# SparkFun_RFM97CW_Breakout.net
KiCad netlist of a schematic drawn in EAGLE
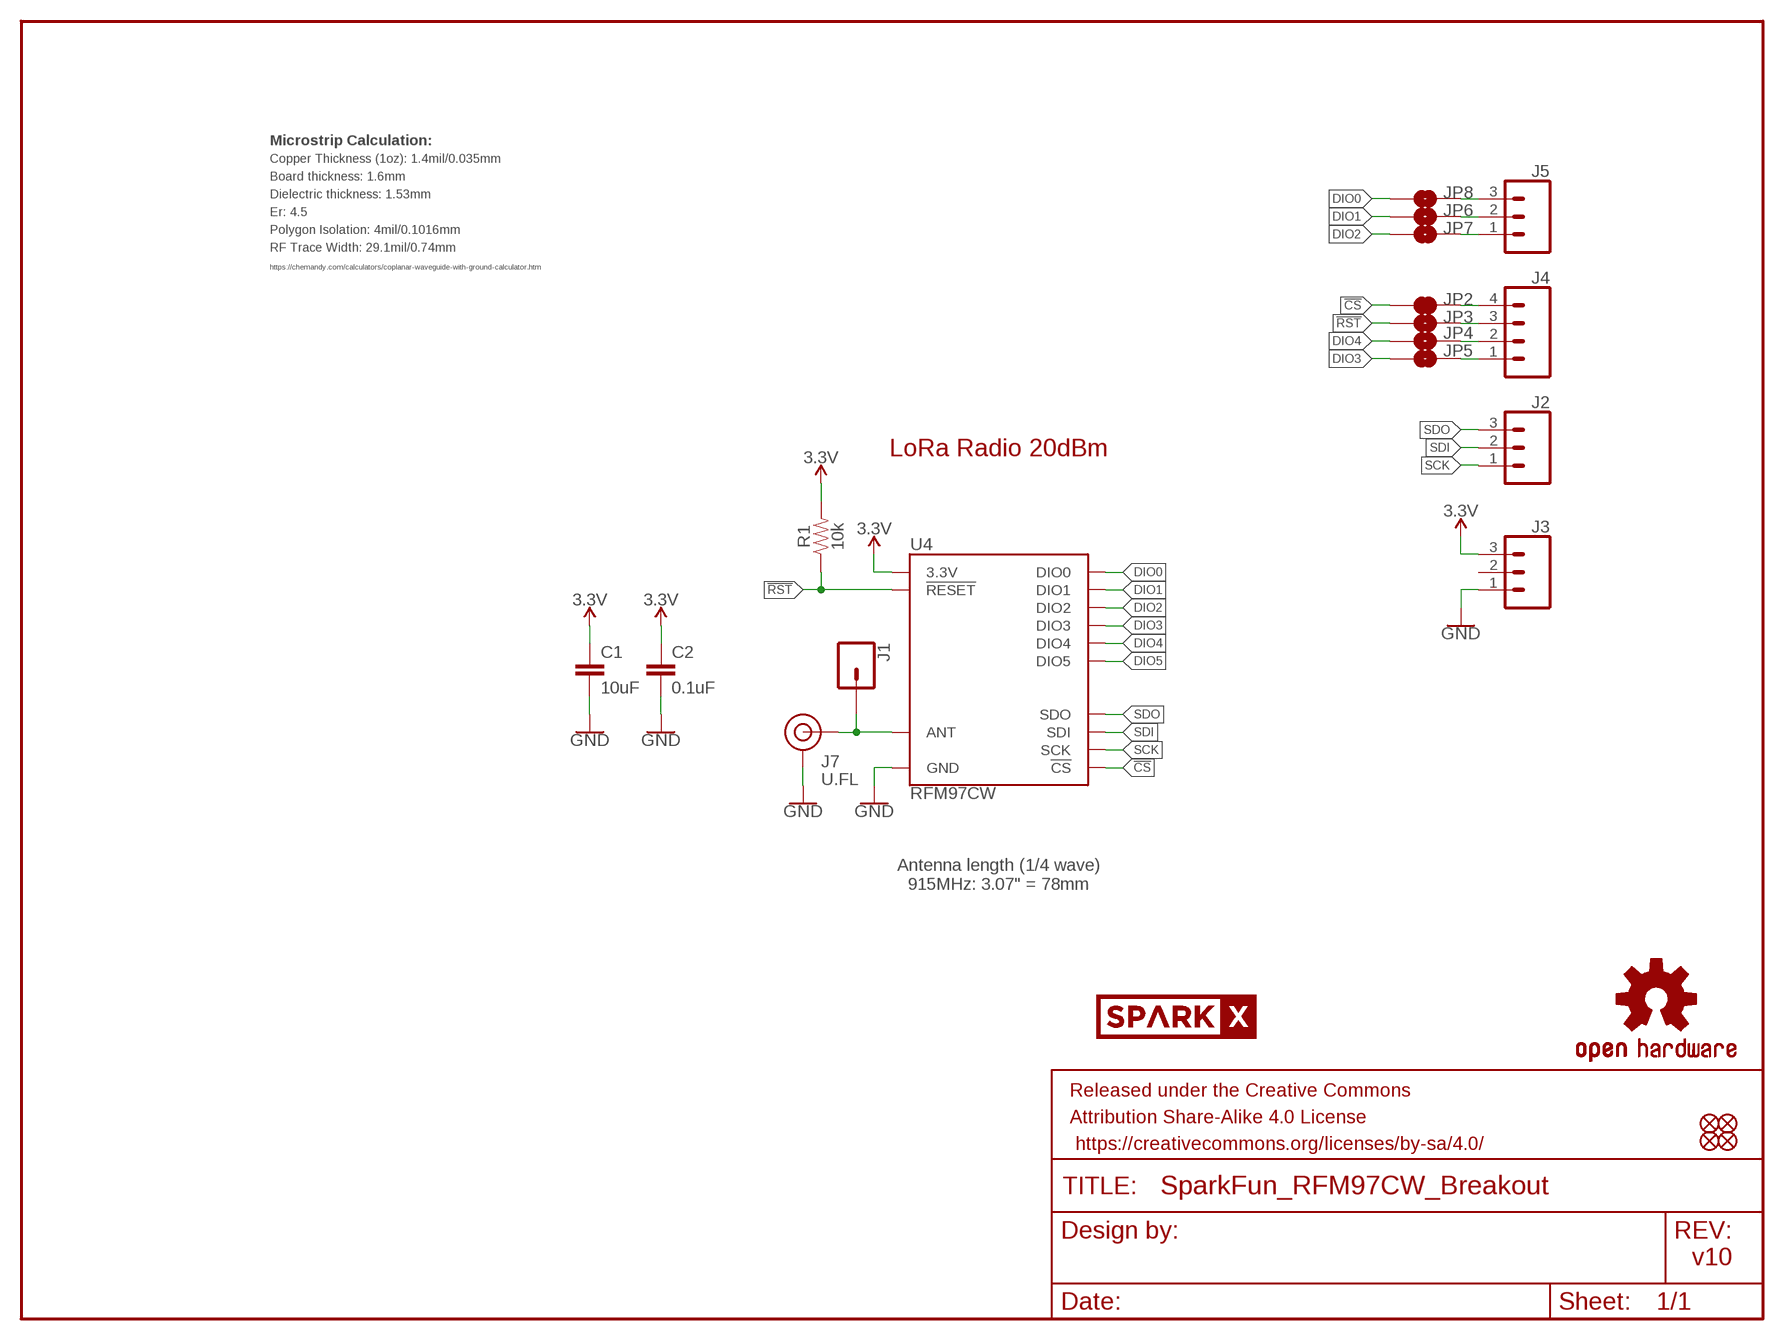
[diagram p0: schematic, sheet 1]

(export (version "E")
  (design (tool "Eeschema 10.0.6"))
  (components
    (comp (ref "C1")
      (value "10uF")
      (footprint "eagle-import:0603")
      (libsource (lib "eagle-import") (part "10UF-0603-6.3V-20%"))
    )
    (comp (ref "C2")
      (value "0.1uF")
      (footprint "eagle-import:0603")
      (libsource (lib "eagle-import") (part "0.1UF-0603-25V-(+80/-20%)"))
    )
    (comp (ref "FID1")
      (value "FIDUCIAL1X2")
      (footprint "eagle-import:FIDUCIAL-1X2")
      (libsource (lib "eagle-import") (part "FIDUCIAL1X2"))
    )
    (comp (ref "FID2")
      (value "FIDUCIAL1X2")
      (footprint "eagle-import:FIDUCIAL-1X2")
      (libsource (lib "eagle-import") (part "FIDUCIAL1X2"))
    )
    (comp (ref "FID3")
      (value "FIDUCIAL1X2")
      (footprint "eagle-import:FIDUCIAL-1X2")
      (libsource (lib "eagle-import") (part "FIDUCIAL1X2"))
    )
    (comp (ref "FID4")
      (value "FIDUCIAL1X2")
      (footprint "eagle-import:FIDUCIAL-1X2")
      (libsource (lib "eagle-import") (part "FIDUCIAL1X2"))
    )
    (comp (ref "FRAME1")
      (value "FRAME-LETTER")
      (footprint "eagle-import:CREATIVE_COMMONS")
      (libsource (lib "eagle-import") (part "FRAME-LETTER"))
    )
    (comp (ref "J1")
      (value "CONN_01PTH_NO_SILK_YES_STOP")
      (footprint "eagle-import:1X01_NO_SILK")
      (libsource (lib "eagle-import") (part "CONN_01PTH_NO_SILK_YES_STOP"))
    )
    (comp (ref "J2")
      (value "CONN_031X03_NO_SILK")
      (footprint "eagle-import:1X03_NO_SILK")
      (libsource (lib "eagle-import") (part "CONN_031X03_NO_SILK"))
    )
    (comp (ref "J3")
      (value "CONN_031X03_NO_SILK")
      (footprint "eagle-import:1X03_NO_SILK")
      (libsource (lib "eagle-import") (part "CONN_031X03_NO_SILK"))
    )
    (comp (ref "J4")
      (value "CONN_041X04_NO_SILK")
      (footprint "eagle-import:1X04_NO_SILK")
      (libsource (lib "eagle-import") (part "CONN_041X04_NO_SILK"))
    )
    (comp (ref "J5")
      (value "CONN_031X03_NO_SILK")
      (footprint "eagle-import:1X03_NO_SILK")
      (libsource (lib "eagle-import") (part "CONN_031X03_NO_SILK"))
    )
    (comp (ref "J7")
      (value "U.FL")
      (footprint "eagle-import:U.FL")
      (libsource (lib "eagle-import") (part "U.FL2PIN"))
    )
    (comp (ref "JP2")
      (value "JUMPER-SMT_2_NC_TRACE_NO-SILK")
      (footprint "eagle-import:SMT-JUMPER_2_NC_TRACE_NO-SILK")
      (libsource (lib "eagle-import") (part "JUMPER-SMT_2_NC_TRACE_NO-SILK"))
    )
    (comp (ref "JP3")
      (value "JUMPER-SMT_2_NO_NO-SILK")
      (footprint "eagle-import:SMT-JUMPER_2_NO_NO-SILK")
      (libsource (lib "eagle-import") (part "JUMPER-SMT_2_NO_NO-SILK"))
    )
    (comp (ref "JP4")
      (value "JUMPER-SMT_2_NO_NO-SILK")
      (footprint "eagle-import:SMT-JUMPER_2_NO_NO-SILK")
      (libsource (lib "eagle-import") (part "JUMPER-SMT_2_NO_NO-SILK"))
    )
    (comp (ref "JP5")
      (value "JUMPER-SMT_2_NO_NO-SILK")
      (footprint "eagle-import:SMT-JUMPER_2_NO_NO-SILK")
      (libsource (lib "eagle-import") (part "JUMPER-SMT_2_NO_NO-SILK"))
    )
    (comp (ref "JP6")
      (value "JUMPER-SMT_2_NO_NO-SILK")
      (footprint "eagle-import:SMT-JUMPER_2_NO_NO-SILK")
      (libsource (lib "eagle-import") (part "JUMPER-SMT_2_NO_NO-SILK"))
    )
    (comp (ref "JP7")
      (value "JUMPER-SMT_2_NO_NO-SILK")
      (footprint "eagle-import:SMT-JUMPER_2_NO_NO-SILK")
      (libsource (lib "eagle-import") (part "JUMPER-SMT_2_NO_NO-SILK"))
    )
    (comp (ref "JP8")
      (value "JUMPER-SMT_2_NO_NO-SILK")
      (footprint "eagle-import:SMT-JUMPER_2_NO_NO-SILK")
      (libsource (lib "eagle-import") (part "JUMPER-SMT_2_NO_NO-SILK"))
    )
    (comp (ref "LOGO2")
      (value "OSHW-LOGOS")
      (footprint "eagle-import:OSHW-LOGO-S")
      (libsource (lib "eagle-import") (part "OSHW-LOGOS"))
    )
    (comp (ref "R1")
      (value "10k")
      (footprint "eagle-import:0603")
      (libsource (lib "eagle-import") (part "10KOHM-0603-1/10W-1%"))
    )
    (comp (ref "U$22")
      (value "SPARKX-LOGO5")
      (footprint "eagle-import:SPARKX-LARGE")
      (libsource (lib "eagle-import") (part "SPARKX-LOGO5"))
    )
    (comp (ref "U4")
      (value "RFM97CW")
      (footprint "eagle-import:RFM97")
      (libsource (lib "eagle-import") (part "RFM9XRFM97"))
    )
  )
  (nets
    (net (code "1") (name "/~{CS}") (class "Default")
      (node (ref "JP2") (pin "1") (pinfunction "1_1") (pintype "passive"))
      (node (ref "U4") (pin "!CS!") (pinfunction "~{CS}_!CS!") (pintype "bidirectional"))
    )
    (net (code "2") (name "/~{RST}") (class "Default")
      (node (ref "JP3") (pin "1") (pinfunction "1_1") (pintype "passive"))
      (node (ref "R1") (pin "1") (pinfunction "1_1") (pintype "passive"))
      (node (ref "U4") (pin "!RST") (pinfunction "~{RESET}_!RST") (pintype "bidirectional"))
    )
    (net (code "3") (name "3.3V") (class "Default")
      (node (ref "C1") (pin "1") (pinfunction "1_1") (pintype "passive"))
      (node (ref "C2") (pin "1") (pinfunction "1_1") (pintype "passive"))
      (node (ref "J3") (pin "3") (pinfunction "3_3") (pintype "passive"))
      (node (ref "R1") (pin "2") (pinfunction "2_2") (pintype "passive"))
      (node (ref "U4") (pin "3V3") (pinfunction "3.3V_3V3") (pintype "bidirectional"))
    )
    (net (code "4") (name "DIO0") (class "Default")
      (node (ref "JP8") (pin "1") (pinfunction "1_1") (pintype "passive"))
      (node (ref "U4") (pin "DIO0") (pinfunction "DIO0_DIO0") (pintype "bidirectional"))
    )
    (net (code "5") (name "DIO1") (class "Default")
      (node (ref "JP6") (pin "1") (pinfunction "1_1") (pintype "passive"))
      (node (ref "U4") (pin "DIO1") (pinfunction "DIO1_DIO1") (pintype "bidirectional"))
    )
    (net (code "6") (name "DIO2") (class "Default")
      (node (ref "JP7") (pin "1") (pinfunction "1_1") (pintype "passive"))
      (node (ref "U4") (pin "DIO2") (pinfunction "DIO2_DIO2") (pintype "bidirectional"))
    )
    (net (code "7") (name "DIO3") (class "Default")
      (node (ref "JP5") (pin "1") (pinfunction "1_1") (pintype "passive"))
      (node (ref "U4") (pin "DIO3") (pinfunction "DIO3_DIO3") (pintype "bidirectional"))
    )
    (net (code "8") (name "DIO4") (class "Default")
      (node (ref "JP4") (pin "1") (pinfunction "1_1") (pintype "passive"))
      (node (ref "U4") (pin "DIO4") (pinfunction "DIO4_DIO4") (pintype "bidirectional"))
    )
    (net (code "9") (name "DIO5") (class "Default")
      (node (ref "U4") (pin "DIO5") (pinfunction "DIO5_DIO5") (pintype "bidirectional"))
    )
    (net (code "10") (name "GND") (class "Default")
      (node (ref "C1") (pin "2") (pinfunction "2_2") (pintype "passive"))
      (node (ref "C2") (pin "2") (pinfunction "2_2") (pintype "passive"))
      (node (ref "J3") (pin "1") (pinfunction "1_1") (pintype "passive"))
      (node (ref "J7") (pin "1") (pinfunction "GND_1") (pintype "bidirectional"))
      (node (ref "J7") (pin "2") (pinfunction "GND_2") (pintype "bidirectional"))
      (node (ref "U4") (pin "GND") (pinfunction "GND_GND") (pintype "bidirectional"))
      (node (ref "U4") (pin "GND@1") (pinfunction "GND_GND@1") (pintype "bidirectional"))
      (node (ref "U4") (pin "GND@2") (pinfunction "GND_GND@2") (pintype "bidirectional"))
    )
    (net (code "11") (name "Net-(J4-Pad1)") (class "Default")
      (node (ref "J4") (pin "1") (pinfunction "1_1") (pintype "passive"))
      (node (ref "JP5") (pin "2") (pinfunction "2_2") (pintype "passive"))
    )
    (net (code "12") (name "Net-(J4-Pad2)") (class "Default")
      (node (ref "J4") (pin "2") (pinfunction "2_2") (pintype "passive"))
      (node (ref "JP4") (pin "2") (pinfunction "2_2") (pintype "passive"))
    )
    (net (code "13") (name "Net-(J4-Pad3)") (class "Default")
      (node (ref "J4") (pin "3") (pinfunction "3_3") (pintype "passive"))
      (node (ref "JP3") (pin "2") (pinfunction "2_2") (pintype "passive"))
    )
    (net (code "14") (name "Net-(J4-Pad4)") (class "Default")
      (node (ref "J4") (pin "4") (pinfunction "4_4") (pintype "passive"))
      (node (ref "JP2") (pin "2") (pinfunction "2_2") (pintype "passive"))
    )
    (net (code "15") (name "Net-(J5-Pad1)") (class "Default")
      (node (ref "J5") (pin "1") (pinfunction "1_1") (pintype "passive"))
      (node (ref "JP7") (pin "2") (pinfunction "2_2") (pintype "passive"))
    )
    (net (code "16") (name "Net-(J5-Pad2)") (class "Default")
      (node (ref "J5") (pin "2") (pinfunction "2_2") (pintype "passive"))
      (node (ref "JP6") (pin "2") (pinfunction "2_2") (pintype "passive"))
    )
    (net (code "17") (name "Net-(J5-Pad3)") (class "Default")
      (node (ref "J5") (pin "3") (pinfunction "3_3") (pintype "passive"))
      (node (ref "JP8") (pin "2") (pinfunction "2_2") (pintype "passive"))
    )
    (net (code "18") (name "Net-(J7-SIGNAL)") (class "Default")
      (node (ref "J1") (pin "1") (pinfunction "1_1") (pintype "passive"))
      (node (ref "J7") (pin "FEED") (pinfunction "SIGNAL_FEED") (pintype "bidirectional"))
      (node (ref "U4") (pin "ANT") (pinfunction "ANT_ANT") (pintype "bidirectional"))
    )
    (net (code "19") (name "SCK") (class "Default")
      (node (ref "J2") (pin "1") (pinfunction "1_1") (pintype "passive"))
      (node (ref "U4") (pin "SCK") (pinfunction "SCK_SCK") (pintype "bidirectional"))
    )
    (net (code "20") (name "SDI") (class "Default")
      (node (ref "J2") (pin "2") (pinfunction "2_2") (pintype "passive"))
      (node (ref "U4") (pin "SDI") (pinfunction "SDI_SDI") (pintype "bidirectional"))
    )
    (net (code "21") (name "SDO") (class "Default")
      (node (ref "J2") (pin "3") (pinfunction "3_3") (pintype "passive"))
      (node (ref "U4") (pin "SDO") (pinfunction "SDO_SDO") (pintype "bidirectional"))
    )
    (net (code "22") (name "unconnected-(J3-Pad2)") (class "Default")
      (node (ref "J3") (pin "2") (pinfunction "2_2") (pintype "passive"))
    )
  )
)
